# Front_DB_handrouted.net
KiCad netlist of a schematic drawn in EAGLE
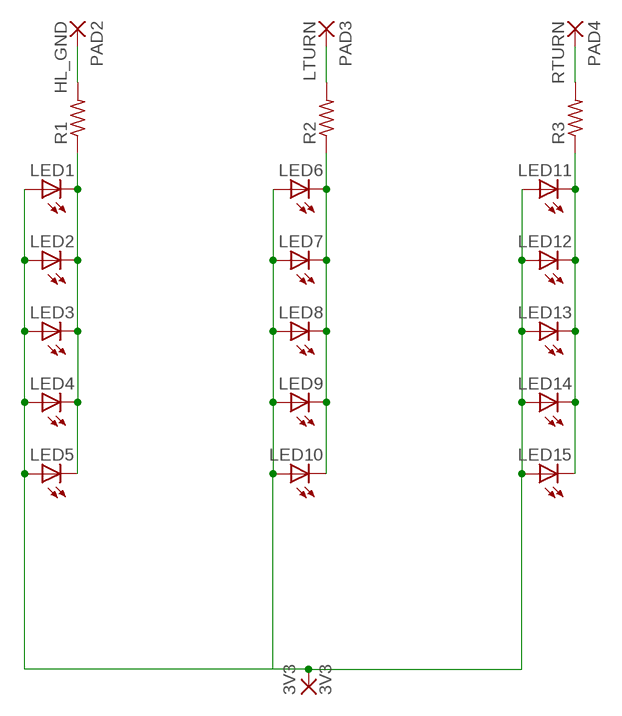
[diagram p0: schematic, sheet 1]

(export (version "E")
  (design (tool "Eeschema 10.0.6"))
  (components
    (comp (ref "3V3")
      (value "3V3")
      (footprint "eagle-import:2,54_1,1")
      (libsource (lib "eagle-import") (part "2,54/1,1"))
    )
    (comp (ref "LED1")
      (value "LEDMICRO-SIDELED")
      (footprint "eagle-import:MICRO-SIDELED")
      (libsource (lib "eagle-import") (part "LEDMICRO-SIDELED"))
    )
    (comp (ref "LED2")
      (value "LEDMICRO-SIDELED")
      (footprint "eagle-import:MICRO-SIDELED")
      (libsource (lib "eagle-import") (part "LEDMICRO-SIDELED"))
    )
    (comp (ref "LED3")
      (value "LEDMICRO-SIDELED")
      (footprint "eagle-import:MICRO-SIDELED")
      (libsource (lib "eagle-import") (part "LEDMICRO-SIDELED"))
    )
    (comp (ref "LED4")
      (value "LEDMICRO-SIDELED")
      (footprint "eagle-import:MICRO-SIDELED")
      (libsource (lib "eagle-import") (part "LEDMICRO-SIDELED"))
    )
    (comp (ref "LED5")
      (value "LEDMICRO-SIDELED")
      (footprint "eagle-import:MICRO-SIDELED")
      (libsource (lib "eagle-import") (part "LEDMICRO-SIDELED"))
    )
    (comp (ref "LED6")
      (value "LEDCHIPLED_0603")
      (footprint "eagle-import:CHIPLED_0603")
      (libsource (lib "eagle-import") (part "LEDCHIPLED_0603"))
    )
    (comp (ref "LED7")
      (value "LEDCHIPLED_0603")
      (footprint "eagle-import:CHIPLED_0603")
      (libsource (lib "eagle-import") (part "LEDCHIPLED_0603"))
    )
    (comp (ref "LED8")
      (value "LEDCHIPLED_0603")
      (footprint "eagle-import:CHIPLED_0603")
      (libsource (lib "eagle-import") (part "LEDCHIPLED_0603"))
    )
    (comp (ref "LED9")
      (value "LEDCHIPLED_0603")
      (footprint "eagle-import:CHIPLED_0603")
      (libsource (lib "eagle-import") (part "LEDCHIPLED_0603"))
    )
    (comp (ref "LED10")
      (value "LEDCHIPLED_0603")
      (footprint "eagle-import:CHIPLED_0603")
      (libsource (lib "eagle-import") (part "LEDCHIPLED_0603"))
    )
    (comp (ref "LED11")
      (value "LEDCHIPLED_0603")
      (footprint "eagle-import:CHIPLED_0603")
      (libsource (lib "eagle-import") (part "LEDCHIPLED_0603"))
    )
    (comp (ref "LED12")
      (value "LEDCHIPLED_0603")
      (footprint "eagle-import:CHIPLED_0603")
      (libsource (lib "eagle-import") (part "LEDCHIPLED_0603"))
    )
    (comp (ref "LED13")
      (value "LEDCHIPLED_0603")
      (footprint "eagle-import:CHIPLED_0603")
      (libsource (lib "eagle-import") (part "LEDCHIPLED_0603"))
    )
    (comp (ref "LED14")
      (value "LEDCHIPLED_0603")
      (footprint "eagle-import:CHIPLED_0603")
      (libsource (lib "eagle-import") (part "LEDCHIPLED_0603"))
    )
    (comp (ref "LED15")
      (value "LEDCHIPLED_0603")
      (footprint "eagle-import:CHIPLED_0603")
      (libsource (lib "eagle-import") (part "LEDCHIPLED_0603"))
    )
    (comp (ref "PAD2")
      (value "HL_GND")
      (footprint "eagle-import:2,54_1,1")
      (libsource (lib "eagle-import") (part "2,54/1,1"))
    )
    (comp (ref "PAD3")
      (value "LTURN")
      (footprint "eagle-import:2,54_1,1")
      (libsource (lib "eagle-import") (part "2,54/1,1"))
    )
    (comp (ref "PAD4")
      (value "RTURN")
      (footprint "eagle-import:2,54_1,1")
      (libsource (lib "eagle-import") (part "2,54/1,1"))
    )
    (comp (ref "R1")
      (value "R-US_R0805")
      (footprint "eagle-import:R0805")
      (libsource (lib "eagle-import") (part "R-US_R0805"))
    )
    (comp (ref "R2")
      (value "R-US_R0805")
      (footprint "eagle-import:R0805")
      (libsource (lib "eagle-import") (part "R-US_R0805"))
    )
    (comp (ref "R3")
      (value "R-US_R0805")
      (footprint "eagle-import:R0805")
      (libsource (lib "eagle-import") (part "R-US_R0805"))
    )
  )
  (nets
    (net (code "1") (name "Net-(3V3-P)") (class "Default")
      (node (ref "3V3") (pin "1") (pinfunction "P_1") (pintype "passive"))
      (node (ref "LED1") (pin "A") (pinfunction "A_A") (pintype "passive"))
      (node (ref "LED10") (pin "A") (pinfunction "A_A") (pintype "passive"))
      (node (ref "LED11") (pin "A") (pinfunction "A_A") (pintype "passive"))
      (node (ref "LED12") (pin "A") (pinfunction "A_A") (pintype "passive"))
      (node (ref "LED13") (pin "A") (pinfunction "A_A") (pintype "passive"))
      (node (ref "LED14") (pin "A") (pinfunction "A_A") (pintype "passive"))
      (node (ref "LED15") (pin "A") (pinfunction "A_A") (pintype "passive"))
      (node (ref "LED2") (pin "A") (pinfunction "A_A") (pintype "passive"))
      (node (ref "LED3") (pin "A") (pinfunction "A_A") (pintype "passive"))
      (node (ref "LED4") (pin "A") (pinfunction "A_A") (pintype "passive"))
      (node (ref "LED5") (pin "A") (pinfunction "A_A") (pintype "passive"))
      (node (ref "LED6") (pin "A") (pinfunction "A_A") (pintype "passive"))
      (node (ref "LED7") (pin "A") (pinfunction "A_A") (pintype "passive"))
      (node (ref "LED8") (pin "A") (pinfunction "A_A") (pintype "passive"))
      (node (ref "LED9") (pin "A") (pinfunction "A_A") (pintype "passive"))
    )
    (net (code "2") (name "Net-(LED1-PadC)") (class "Default")
      (node (ref "LED1") (pin "C") (pinfunction "C_C") (pintype "passive"))
      (node (ref "LED2") (pin "C") (pinfunction "C_C") (pintype "passive"))
      (node (ref "LED3") (pin "C") (pinfunction "C_C") (pintype "passive"))
      (node (ref "LED4") (pin "C") (pinfunction "C_C") (pintype "passive"))
      (node (ref "LED5") (pin "C") (pinfunction "C_C") (pintype "passive"))
      (node (ref "R1") (pin "1") (pinfunction "1_1") (pintype "passive"))
    )
    (net (code "3") (name "Net-(LED10-PadC)") (class "Default")
      (node (ref "LED10") (pin "C") (pinfunction "C_C") (pintype "passive"))
      (node (ref "LED6") (pin "C") (pinfunction "C_C") (pintype "passive"))
      (node (ref "LED7") (pin "C") (pinfunction "C_C") (pintype "passive"))
      (node (ref "LED8") (pin "C") (pinfunction "C_C") (pintype "passive"))
      (node (ref "LED9") (pin "C") (pinfunction "C_C") (pintype "passive"))
      (node (ref "R2") (pin "1") (pinfunction "1_1") (pintype "passive"))
    )
    (net (code "4") (name "Net-(LED11-PadC)") (class "Default")
      (node (ref "LED11") (pin "C") (pinfunction "C_C") (pintype "passive"))
      (node (ref "LED12") (pin "C") (pinfunction "C_C") (pintype "passive"))
      (node (ref "LED13") (pin "C") (pinfunction "C_C") (pintype "passive"))
      (node (ref "LED14") (pin "C") (pinfunction "C_C") (pintype "passive"))
      (node (ref "LED15") (pin "C") (pinfunction "C_C") (pintype "passive"))
      (node (ref "R3") (pin "1") (pinfunction "1_1") (pintype "passive"))
    )
    (net (code "5") (name "Net-(PAD2-P)") (class "Default")
      (node (ref "PAD2") (pin "1") (pinfunction "P_1") (pintype "passive"))
      (node (ref "R1") (pin "2") (pinfunction "2_2") (pintype "passive"))
    )
    (net (code "6") (name "Net-(PAD3-P)") (class "Default")
      (node (ref "PAD3") (pin "1") (pinfunction "P_1") (pintype "passive"))
      (node (ref "R2") (pin "2") (pinfunction "2_2") (pintype "passive"))
    )
    (net (code "7") (name "Net-(PAD4-P)") (class "Default")
      (node (ref "PAD4") (pin "1") (pinfunction "P_1") (pintype "passive"))
      (node (ref "R3") (pin "2") (pinfunction "2_2") (pintype "passive"))
    )
  )
)
